# AXAWIFI.net
KiCad netlist of a schematic drawn in EAGLE
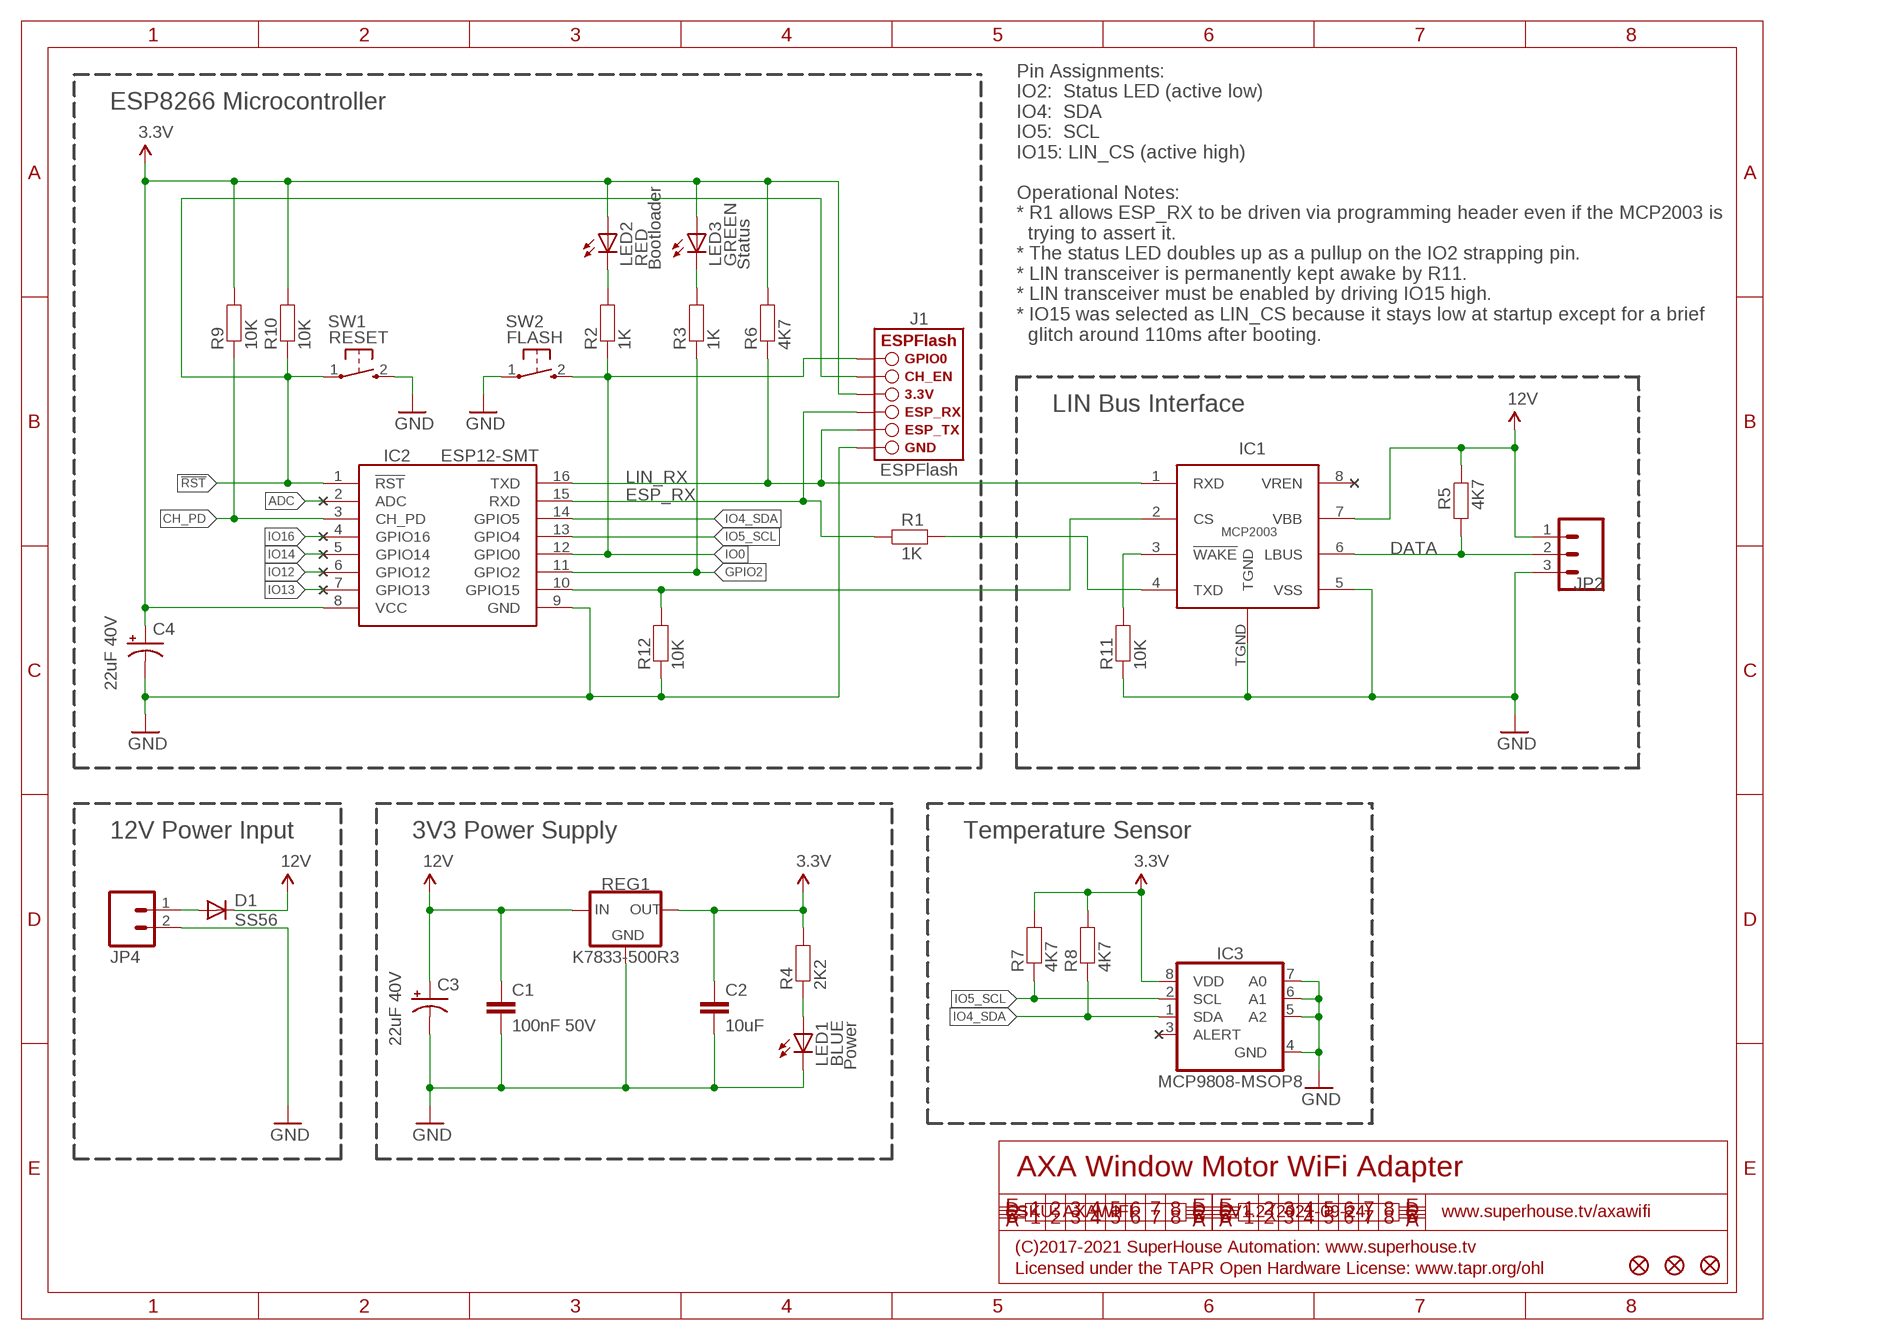
[diagram p0: schematic, sheet 1]

(export (version "E")
  (design (tool "Eeschema 10.0.6"))
  (components
    (comp (ref "C1")
      (value "100nF 50V")
      (footprint "eagle-import:C0603")
      (libsource (lib "eagle-import") (part "CAP0603"))
    )
    (comp (ref "C2")
      (value "10uF")
      (footprint "eagle-import:C0805")
      (libsource (lib "eagle-import") (part "CAP0805"))
    )
    (comp (ref "C3")
      (value "22uF 40V")
      (footprint "eagle-import:PANASONIC_C")
      (libsource (lib "eagle-import") (part "CAP_POLC"))
    )
    (comp (ref "C4")
      (value "22uF 40V")
      (footprint "eagle-import:PANASONIC_C")
      (libsource (lib "eagle-import") (part "CAP_POLC"))
    )
    (comp (ref "D1")
      (value "SS56")
      (footprint "eagle-import:SMA-DIODE")
      (libsource (lib "eagle-import") (part "DIODESMA"))
    )
    (comp (ref "FID1")
      (value "FIDUCIAL1X2.5")
      (footprint "eagle-import:FIDUCIAL-1X2.5")
      (libsource (lib "eagle-import") (part "FIDUCIAL1X2.5"))
    )
    (comp (ref "FID2")
      (value "FIDUCIAL1X2.5")
      (footprint "eagle-import:FIDUCIAL-1X2.5")
      (libsource (lib "eagle-import") (part "FIDUCIAL1X2.5"))
    )
    (comp (ref "FID3")
      (value "FIDUCIAL1X2.5")
      (footprint "eagle-import:FIDUCIAL-1X2.5")
      (libsource (lib "eagle-import") (part "FIDUCIAL1X2.5"))
    )
    (comp (ref "IC1")
      (value "MCP2003")
      (footprint "eagle-import:SOIC8T")
      (libsource (lib "eagle-import") (part "MCP2003"))
    )
    (comp (ref "IC2")
      (value "ESP12-SMT")
      (footprint "eagle-import:ESP12")
      (libsource (lib "eagle-import") (part "ESP12-SMT"))
    )
    (comp (ref "IC3")
      (value "MCP9808-MSOP8")
      (footprint "eagle-import:MSOP-8")
      (libsource (lib "eagle-import") (part "MCP9808-MSOP8"))
    )
    (comp (ref "J1")
      (value "ESPFLASH-1X6-2.54-SOCKET")
      (footprint "eagle-import:1X6-2.54-SOCKET")
      (libsource (lib "eagle-import") (part "ESPFLASH-1X6-2.54-SOCKET"))
    )
    (comp (ref "JP2")
      (value "M03-PLAIN")
      (footprint "eagle-import:1X03")
      (libsource (lib "eagle-import") (part "M03-PLAIN"))
    )
    (comp (ref "JP4")
      (value "M02-SCREW-3.5MM")
      (footprint "eagle-import:SCREWTERMINAL-3.5MM-2")
      (libsource (lib "eagle-import") (part "M02-SCREW-3.5MM"))
    )
    (comp (ref "LED1")
      (value "BLUE")
      (footprint "eagle-import:LED-0603")
      (libsource (lib "eagle-import") (part "LED0603"))
    )
    (comp (ref "LED2")
      (value "RED")
      (footprint "eagle-import:LED-0603")
      (libsource (lib "eagle-import") (part "LED0603"))
    )
    (comp (ref "LED3")
      (value "GREEN")
      (footprint "eagle-import:LED-0603")
      (libsource (lib "eagle-import") (part "LED0603"))
    )
    (comp (ref "R1")
      (value "1K")
      (footprint "eagle-import:R0603")
      (libsource (lib "eagle-import") (part "RESISTOR0603"))
    )
    (comp (ref "R2")
      (value "1K")
      (footprint "eagle-import:R0603")
      (libsource (lib "eagle-import") (part "RESISTOR0603"))
    )
    (comp (ref "R3")
      (value "1K")
      (footprint "eagle-import:R0603")
      (libsource (lib "eagle-import") (part "RESISTOR0603"))
    )
    (comp (ref "R4")
      (value "2K2")
      (footprint "eagle-import:R0603")
      (libsource (lib "eagle-import") (part "RESISTOR0603"))
    )
    (comp (ref "R5")
      (value "4K7")
      (footprint "eagle-import:R0603")
      (libsource (lib "eagle-import") (part "RESISTOR0603"))
    )
    (comp (ref "R6")
      (value "4K7")
      (footprint "eagle-import:R0603")
      (libsource (lib "eagle-import") (part "RESISTOR0603"))
    )
    (comp (ref "R7")
      (value "4K7")
      (footprint "eagle-import:R0603")
      (libsource (lib "eagle-import") (part "RESISTOR0603"))
    )
    (comp (ref "R8")
      (value "4K7")
      (footprint "eagle-import:R0603")
      (libsource (lib "eagle-import") (part "RESISTOR0603"))
    )
    (comp (ref "R9")
      (value "10K")
      (footprint "eagle-import:R0603")
      (libsource (lib "eagle-import") (part "RESISTOR0603"))
    )
    (comp (ref "R10")
      (value "10K")
      (footprint "eagle-import:R0603")
      (libsource (lib "eagle-import") (part "RESISTOR0603"))
    )
    (comp (ref "R11")
      (value "10K")
      (footprint "eagle-import:R0603")
      (libsource (lib "eagle-import") (part "RESISTOR0603"))
    )
    (comp (ref "R12")
      (value "10K")
      (footprint "eagle-import:R0603")
      (libsource (lib "eagle-import") (part "RESISTOR0603"))
    )
    (comp (ref "REG1")
      (value "K7833-500R3")
      (footprint "eagle-import:K78XX-500R3")
      (libsource (lib "eagle-import") (part "78XX-K78XX-VERTICAL"))
    )
    (comp (ref "SW1")
      (value "RESET")
      (footprint "eagle-import:TACTILE_SMT_3X4X2")
      (libsource (lib "eagle-import") (part "TAC_SWITCH_2PINSMT"))
    )
    (comp (ref "SW2")
      (value "FLASH")
      (footprint "eagle-import:TACTILE_SMT_3X4X2")
      (libsource (lib "eagle-import") (part "TAC_SWITCH_2PINSMT"))
    )
  )
  (nets
    (net (code "1") (name "/DATA") (class "Default")
      (node (ref "IC1") (pin "6") (pinfunction "LBUS_6") (pintype "bidirectional"))
      (node (ref "JP2") (pin "2") (pinfunction "2_2") (pintype "passive"))
      (node (ref "R5") (pin "1") (pinfunction "1_1") (pintype "passive"))
    )
    (net (code "2") (name "/ESP_RX") (class "Default")
      (node (ref "IC2") (pin "15") (pinfunction "RXD_15") (pintype "input"))
      (node (ref "J1") (pin "3") (pinfunction "ESP_RX_3") (pintype "passive"))
      (node (ref "R1") (pin "1") (pinfunction "1_1") (pintype "passive"))
    )
    (net (code "3") (name "/LIN_RX") (class "Default")
      (node (ref "IC1") (pin "1") (pinfunction "RXD_1") (pintype "input"))
      (node (ref "IC2") (pin "16") (pinfunction "TXD_16") (pintype "output"))
      (node (ref "J1") (pin "2") (pinfunction "ESP_TX_2") (pintype "passive"))
      (node (ref "R6") (pin "1") (pinfunction "1_1") (pintype "passive"))
    )
    (net (code "4") (name "/~{RST}") (class "Default")
      (node (ref "IC2") (pin "1") (pinfunction "~{RST}_1") (pintype "bidirectional"))
      (node (ref "J1") (pin "5") (pinfunction "CH_EN_5") (pintype "passive"))
      (node (ref "R10") (pin "1") (pinfunction "1_1") (pintype "passive"))
      (node (ref "SW1") (pin "1") (pinfunction "P_1") (pintype "passive"))
    )
    (net (code "5") (name "3.3V") (class "Default")
      (node (ref "C2") (pin "1") (pinfunction "1_1") (pintype "passive"))
      (node (ref "C4") (pin "+") (pinfunction "+_+") (pintype "passive"))
      (node (ref "IC2") (pin "8") (pinfunction "VCC_8") (pintype "power_in"))
      (node (ref "IC3") (pin "8") (pinfunction "VDD_8") (pintype "bidirectional"))
      (node (ref "J1") (pin "4") (pinfunction "3.3V_4") (pintype "passive"))
      (node (ref "LED2") (pin "A") (pinfunction "A_A") (pintype "passive"))
      (node (ref "LED3") (pin "A") (pinfunction "A_A") (pintype "passive"))
      (node (ref "R10") (pin "2") (pinfunction "2_2") (pintype "passive"))
      (node (ref "R4") (pin "2") (pinfunction "2_2") (pintype "passive"))
      (node (ref "R6") (pin "2") (pinfunction "2_2") (pintype "passive"))
      (node (ref "R7") (pin "2") (pinfunction "2_2") (pintype "passive"))
      (node (ref "R8") (pin "2") (pinfunction "2_2") (pintype "passive"))
      (node (ref "R9") (pin "2") (pinfunction "2_2") (pintype "passive"))
      (node (ref "REG1") (pin "3") (pinfunction "OUT_3") (pintype "output"))
    )
    (net (code "6") (name "12V") (class "Default")
      (node (ref "C1") (pin "1") (pinfunction "1_1") (pintype "passive"))
      (node (ref "C3") (pin "+") (pinfunction "+_+") (pintype "passive"))
      (node (ref "D1") (pin "C") (pinfunction "C_C") (pintype "passive"))
      (node (ref "IC1") (pin "7") (pinfunction "VBB_7") (pintype "power_in"))
      (node (ref "JP2") (pin "1") (pinfunction "1_1") (pintype "passive"))
      (node (ref "R5") (pin "2") (pinfunction "2_2") (pintype "passive"))
      (node (ref "REG1") (pin "1") (pinfunction "IN_1") (pintype "input"))
    )
    (net (code "7") (name "ADC") (class "Default")
      (node (ref "IC2") (pin "2") (pinfunction "ADC_2") (pintype "input"))
    )
    (net (code "8") (name "CH_PD") (class "Default")
      (node (ref "IC2") (pin "3") (pinfunction "CH_PD_3") (pintype "input"))
      (node (ref "R9") (pin "1") (pinfunction "1_1") (pintype "passive"))
    )
    (net (code "9") (name "GND") (class "Default")
      (node (ref "C1") (pin "2") (pinfunction "2_2") (pintype "passive"))
      (node (ref "C2") (pin "2") (pinfunction "2_2") (pintype "passive"))
      (node (ref "C3") (pin "-") (pinfunction "-_-") (pintype "passive"))
      (node (ref "C4") (pin "-") (pinfunction "-_-") (pintype "passive"))
      (node (ref "IC1") (pin "5") (pinfunction "VSS_5") (pintype "power_in"))
      (node (ref "IC1") (pin "TGND") (pinfunction "TGND_TGND") (pintype "power_in"))
      (node (ref "IC2") (pin "9") (pinfunction "GND_9") (pintype "power_in"))
      (node (ref "IC3") (pin "4") (pinfunction "GND_4") (pintype "bidirectional"))
      (node (ref "IC3") (pin "5") (pinfunction "A2_5") (pintype "bidirectional"))
      (node (ref "IC3") (pin "6") (pinfunction "A1_6") (pintype "bidirectional"))
      (node (ref "IC3") (pin "7") (pinfunction "A0_7") (pintype "bidirectional"))
      (node (ref "J1") (pin "1") (pinfunction "GND_1") (pintype "passive"))
      (node (ref "JP2") (pin "3") (pinfunction "3_3") (pintype "passive"))
      (node (ref "JP4") (pin "2") (pinfunction "2_2") (pintype "passive"))
      (node (ref "LED1") (pin "C") (pinfunction "C_C") (pintype "passive"))
      (node (ref "R11") (pin "1") (pinfunction "1_1") (pintype "passive"))
      (node (ref "R12") (pin "1") (pinfunction "1_1") (pintype "passive"))
      (node (ref "REG1") (pin "2") (pinfunction "GND_2") (pintype "input"))
      (node (ref "SW1") (pin "2") (pinfunction "S_2") (pintype "passive"))
      (node (ref "SW2") (pin "1") (pinfunction "P_1") (pintype "passive"))
    )
    (net (code "10") (name "GPIO2") (class "Default")
      (node (ref "IC2") (pin "11") (pinfunction "GPIO2_11") (pintype "bidirectional"))
      (node (ref "R3") (pin "1") (pinfunction "1_1") (pintype "passive"))
    )
    (net (code "11") (name "IO0") (class "Default")
      (node (ref "IC2") (pin "12") (pinfunction "GPIO0_12") (pintype "bidirectional"))
      (node (ref "J1") (pin "6") (pinfunction "GPIO0_6") (pintype "passive"))
      (node (ref "R2") (pin "1") (pinfunction "1_1") (pintype "passive"))
      (node (ref "SW2") (pin "2") (pinfunction "S_2") (pintype "passive"))
    )
    (net (code "12") (name "IO4_SDA") (class "Default")
      (node (ref "IC2") (pin "14") (pinfunction "GPIO5_14") (pintype "bidirectional"))
      (node (ref "IC3") (pin "1") (pinfunction "SDA_1") (pintype "bidirectional"))
      (node (ref "R8") (pin "1") (pinfunction "1_1") (pintype "passive"))
    )
    (net (code "13") (name "IO5_SCL") (class "Default")
      (node (ref "IC2") (pin "13") (pinfunction "GPIO4_13") (pintype "bidirectional"))
      (node (ref "IC3") (pin "2") (pinfunction "SCL_2") (pintype "bidirectional"))
      (node (ref "R7") (pin "1") (pinfunction "1_1") (pintype "passive"))
    )
    (net (code "14") (name "IO12") (class "Default")
      (node (ref "IC2") (pin "6") (pinfunction "GPIO12_6") (pintype "bidirectional"))
    )
    (net (code "15") (name "IO13") (class "Default")
      (node (ref "IC2") (pin "7") (pinfunction "GPIO13_7") (pintype "bidirectional"))
    )
    (net (code "16") (name "IO14") (class "Default")
      (node (ref "IC2") (pin "5") (pinfunction "GPIO14_5") (pintype "bidirectional"))
    )
    (net (code "17") (name "IO16") (class "Default")
      (node (ref "IC2") (pin "4") (pinfunction "GPIO16_4") (pintype "bidirectional"))
    )
    (net (code "18") (name "Net-(D1-PadA)") (class "Default")
      (node (ref "D1") (pin "A") (pinfunction "A_A") (pintype "passive"))
      (node (ref "JP4") (pin "1") (pinfunction "1_1") (pintype "passive"))
    )
    (net (code "19") (name "Net-(IC1-CS)") (class "Default")
      (node (ref "IC1") (pin "2") (pinfunction "CS_2") (pintype "input"))
      (node (ref "IC2") (pin "10") (pinfunction "GPIO15_10") (pintype "bidirectional"))
      (node (ref "R12") (pin "2") (pinfunction "2_2") (pintype "passive"))
    )
    (net (code "20") (name "Net-(IC1-TXD)") (class "Default")
      (node (ref "IC1") (pin "4") (pinfunction "TXD_4") (pintype "output"))
      (node (ref "R1") (pin "2") (pinfunction "2_2") (pintype "passive"))
    )
    (net (code "21") (name "Net-(IC1-~{WAKE})") (class "Default")
      (node (ref "IC1") (pin "3") (pinfunction "~{WAKE}_3") (pintype "input"))
      (node (ref "R11") (pin "2") (pinfunction "2_2") (pintype "passive"))
    )
    (net (code "22") (name "Net-(LED1-PadA)") (class "Default")
      (node (ref "LED1") (pin "A") (pinfunction "A_A") (pintype "passive"))
      (node (ref "R4") (pin "1") (pinfunction "1_1") (pintype "passive"))
    )
    (net (code "23") (name "Net-(LED2-PadC)") (class "Default")
      (node (ref "LED2") (pin "C") (pinfunction "C_C") (pintype "passive"))
      (node (ref "R2") (pin "2") (pinfunction "2_2") (pintype "passive"))
    )
    (net (code "24") (name "Net-(LED3-PadC)") (class "Default")
      (node (ref "LED3") (pin "C") (pinfunction "C_C") (pintype "passive"))
      (node (ref "R3") (pin "2") (pinfunction "2_2") (pintype "passive"))
    )
    (net (code "25") (name "unconnected-(IC1-VREN-Pad8)") (class "Default")
      (node (ref "IC1") (pin "8") (pinfunction "VREN_8") (pintype "output"))
    )
    (net (code "26") (name "unconnected-(IC3-ALERT-Pad3)") (class "Default")
      (node (ref "IC3") (pin "3") (pinfunction "ALERT_3") (pintype "bidirectional"))
    )
  )
)
